# LoRa_1W_Breakout.net
KiCad netlist of a schematic drawn in EAGLE
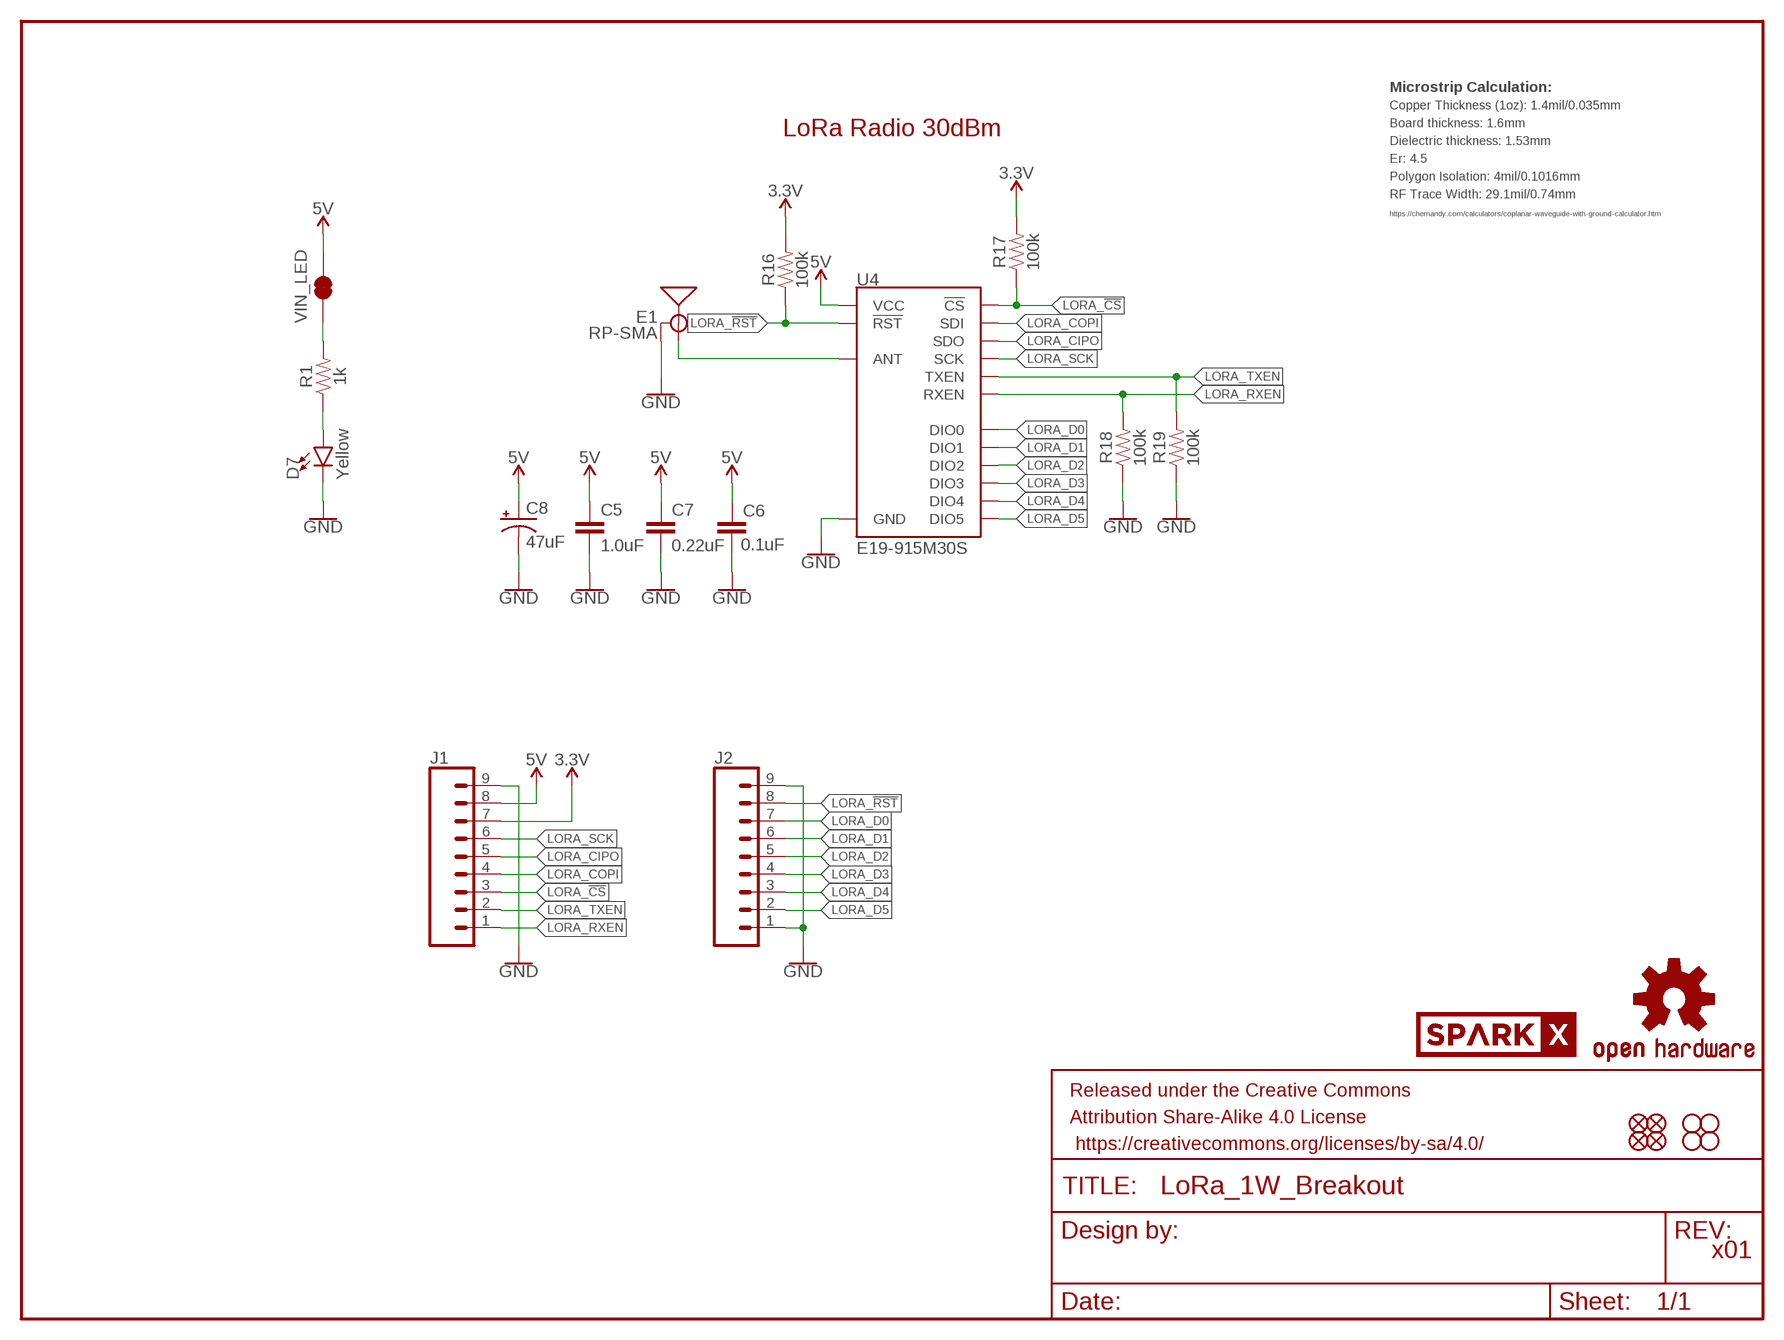
[diagram p0: schematic, sheet 1]

(export (version "E")
  (design (tool "Eeschema 10.0.6"))
  (components
    (comp (ref "C5")
      (value "1.0uF")
      (footprint "eagle-import:0603")
      (libsource (lib "eagle-import") (part "1.0UF-0603-16V-10%"))
    )
    (comp (ref "C6")
      (value "0.1uF")
      (footprint "eagle-import:0603")
      (libsource (lib "eagle-import") (part "0.1UF-0603-25V-(+80/-20%)"))
    )
    (comp (ref "C7")
      (value "0.22uF")
      (footprint "eagle-import:0603")
      (libsource (lib "eagle-import") (part "0.22UF-0603-25V-10%"))
    )
    (comp (ref "C8")
      (value "47uF")
      (footprint "eagle-import:EIA3528")
      (libsource (lib "eagle-import") (part "47UF-POLAR-EIA3528-10V-10%"))
    )
    (comp (ref "D7")
      (value "Yellow")
      (footprint "eagle-import:LED-0603")
      (libsource (lib "eagle-import") (part "LED-YELLOW0603"))
    )
    (comp (ref "E1")
      (value "RP-SMA")
      (footprint "eagle-import:SMA-EDGE")
      (libsource (lib "eagle-import") (part "ANTENNA-SMA-GROUNDEDEDGE_RPSMA"))
    )
    (comp (ref "FD1")
      (value "FIDUCIALUFIDUCIAL")
      (footprint "eagle-import:FIDUCIAL-MICRO")
      (libsource (lib "eagle-import") (part "FIDUCIALUFIDUCIAL"))
    )
    (comp (ref "FD2")
      (value "FIDUCIALUFIDUCIAL")
      (footprint "eagle-import:FIDUCIAL-MICRO")
      (libsource (lib "eagle-import") (part "FIDUCIALUFIDUCIAL"))
    )
    (comp (ref "FD3")
      (value "FIDUCIALUFIDUCIAL")
      (footprint "eagle-import:FIDUCIAL-MICRO")
      (libsource (lib "eagle-import") (part "FIDUCIALUFIDUCIAL"))
    )
    (comp (ref "FD4")
      (value "FIDUCIALUFIDUCIAL")
      (footprint "eagle-import:FIDUCIAL-MICRO")
      (libsource (lib "eagle-import") (part "FIDUCIALUFIDUCIAL"))
    )
    (comp (ref "FRAME2")
      (value "FRAME-LETTER")
      (footprint "eagle-import:CREATIVE_COMMONS")
      (libsource (lib "eagle-import") (part "FRAME-LETTER"))
    )
    (comp (ref "H1")
      (value "STAND-OFF")
      (footprint "eagle-import:STAND-OFF")
      (libsource (lib "eagle-import") (part "STAND-OFF"))
    )
    (comp (ref "H2")
      (value "STAND-OFF")
      (footprint "eagle-import:STAND-OFF")
      (libsource (lib "eagle-import") (part "STAND-OFF"))
    )
    (comp (ref "H3")
      (value "STAND-OFF")
      (footprint "eagle-import:STAND-OFF")
      (libsource (lib "eagle-import") (part "STAND-OFF"))
    )
    (comp (ref "H4")
      (value "STAND-OFF")
      (footprint "eagle-import:STAND-OFF")
      (libsource (lib "eagle-import") (part "STAND-OFF"))
    )
    (comp (ref "J1")
      (value "CONN_09NO_SILK")
      (footprint "eagle-import:1X09_NO_SILK")
      (libsource (lib "eagle-import") (part "CONN_09NO_SILK"))
    )
    (comp (ref "J2")
      (value "CONN_09NO_SILK")
      (footprint "eagle-import:1X09_NO_SILK")
      (libsource (lib "eagle-import") (part "CONN_09NO_SILK"))
    )
    (comp (ref "LOGO3")
      (value "OSHW-LOGOMINI")
      (footprint "eagle-import:OSHW-LOGO-MINI")
      (libsource (lib "eagle-import") (part "OSHW-LOGOMINI"))
    )
    (comp (ref "R1")
      (value "1k")
      (footprint "eagle-import:0603")
      (libsource (lib "eagle-import") (part "1KOHM-0603-1/10W-1%"))
    )
    (comp (ref "R16")
      (value "100k")
      (footprint "eagle-import:0603")
      (libsource (lib "eagle-import") (part "100KOHM-0603-1/10W-1%"))
    )
    (comp (ref "R17")
      (value "100k")
      (footprint "eagle-import:0603")
      (libsource (lib "eagle-import") (part "100KOHM-0603-1/10W-1%"))
    )
    (comp (ref "R18")
      (value "100k")
      (footprint "eagle-import:0603")
      (libsource (lib "eagle-import") (part "100KOHM-0603-1/10W-1%"))
    )
    (comp (ref "R19")
      (value "100k")
      (footprint "eagle-import:0603")
      (libsource (lib "eagle-import") (part "100KOHM-0603-1/10W-1%"))
    )
    (comp (ref "U$5")
      (value "SPARKX-LOGO5")
      (footprint "eagle-import:SPARKX-LARGE")
      (libsource (lib "eagle-import") (part "SPARKX-LOGO5"))
    )
    (comp (ref "U4")
      (value "E19-915M30S")
      (footprint "eagle-import:E19-915MS1W")
      (libsource (lib "eagle-import") (part "E19-915MS1W"))
    )
    (comp (ref "VIN_LED")
      (value "JUMPER-SMT_2_NC_TRACE_SILK")
      (footprint "eagle-import:SMT-JUMPER_2_NC_TRACE_SILK")
      (libsource (lib "eagle-import") (part "JUMPER-SMT_2_NC_TRACE_SILK"))
    )
  )
  (nets
    (net (code "1") (name "/LORA_~{CS}") (class "Default")
      (node (ref "J1") (pin "3") (pinfunction "3_3") (pintype "passive"))
      (node (ref "R17") (pin "1") (pinfunction "1_1") (pintype "passive"))
      (node (ref "U4") (pin "15") (pinfunction "~{CS}_15") (pintype "bidirectional"))
    )
    (net (code "2") (name "/LORA_~{RST}") (class "Default")
      (node (ref "J2") (pin "8") (pinfunction "8_8") (pintype "passive"))
      (node (ref "R16") (pin "1") (pinfunction "1_1") (pintype "passive"))
      (node (ref "U4") (pin "8") (pinfunction "~{RST}_8") (pintype "bidirectional"))
    )
    (net (code "3") (name "3.3V") (class "Default")
      (node (ref "J1") (pin "7") (pinfunction "7_7") (pintype "passive"))
      (node (ref "R16") (pin "2") (pinfunction "2_2") (pintype "passive"))
      (node (ref "R17") (pin "2") (pinfunction "2_2") (pintype "passive"))
    )
    (net (code "4") (name "5V") (class "Default")
      (node (ref "C5") (pin "1") (pinfunction "1_1") (pintype "passive"))
      (node (ref "C6") (pin "1") (pinfunction "1_1") (pintype "passive"))
      (node (ref "C7") (pin "1") (pinfunction "1_1") (pintype "passive"))
      (node (ref "C8") (pin "A") (pinfunction "+_A") (pintype "passive"))
      (node (ref "J1") (pin "8") (pinfunction "8_8") (pintype "passive"))
      (node (ref "U4") (pin "11") (pinfunction "VCC_11") (pintype "bidirectional"))
      (node (ref "VIN_LED") (pin "2") (pinfunction "2_2") (pintype "passive"))
    )
    (net (code "5") (name "GND") (class "Default")
      (node (ref "C5") (pin "2") (pinfunction "2_2") (pintype "passive"))
      (node (ref "C6") (pin "2") (pinfunction "2_2") (pintype "passive"))
      (node (ref "C7") (pin "2") (pinfunction "2_2") (pintype "passive"))
      (node (ref "C8") (pin "C") (pinfunction "-_C") (pintype "passive"))
      (node (ref "D7") (pin "C") (pinfunction "C_C") (pintype "passive"))
      (node (ref "E1") (pin "GND@0") (pinfunction "GND_GND@0") (pintype "bidirectional"))
      (node (ref "E1") (pin "GND@1") (pinfunction "GND_GND@1") (pintype "bidirectional"))
      (node (ref "E1") (pin "GND@2") (pinfunction "GND_GND@2") (pintype "bidirectional"))
      (node (ref "E1") (pin "GND@3") (pinfunction "GND_GND@3") (pintype "bidirectional"))
      (node (ref "J1") (pin "9") (pinfunction "9_9") (pintype "passive"))
      (node (ref "J2") (pin "1") (pinfunction "1_1") (pintype "passive"))
      (node (ref "J2") (pin "9") (pinfunction "9_9") (pintype "passive"))
      (node (ref "R18") (pin "1") (pinfunction "1_1") (pintype "passive"))
      (node (ref "R19") (pin "1") (pinfunction "1_1") (pintype "passive"))
      (node (ref "U4") (pin "1") (pinfunction "GND_1") (pintype "bidirectional"))
      (node (ref "U4") (pin "10") (pinfunction "GND_10") (pintype "bidirectional"))
      (node (ref "U4") (pin "18") (pinfunction "GND_18") (pintype "bidirectional"))
      (node (ref "U4") (pin "20") (pinfunction "GND_20") (pintype "bidirectional"))
      (node (ref "U4") (pin "21") (pinfunction "GND_21") (pintype "bidirectional"))
      (node (ref "U4") (pin "22") (pinfunction "GND_22") (pintype "bidirectional"))
      (node (ref "U4") (pin "9") (pinfunction "GND_9") (pintype "bidirectional"))
    )
    (net (code "6") (name "LORA_CIPO") (class "Default")
      (node (ref "J1") (pin "5") (pinfunction "5_5") (pintype "passive"))
      (node (ref "U4") (pin "13") (pinfunction "SDO_13") (pintype "bidirectional"))
    )
    (net (code "7") (name "LORA_COPI") (class "Default")
      (node (ref "J1") (pin "4") (pinfunction "4_4") (pintype "passive"))
      (node (ref "U4") (pin "14") (pinfunction "SDI_14") (pintype "bidirectional"))
    )
    (net (code "8") (name "LORA_D0") (class "Default")
      (node (ref "J2") (pin "7") (pinfunction "7_7") (pintype "passive"))
      (node (ref "U4") (pin "7") (pinfunction "DIO0_7") (pintype "bidirectional"))
    )
    (net (code "9") (name "LORA_D1") (class "Default")
      (node (ref "J2") (pin "6") (pinfunction "6_6") (pintype "passive"))
      (node (ref "U4") (pin "6") (pinfunction "DIO1_6") (pintype "bidirectional"))
    )
    (net (code "10") (name "LORA_D2") (class "Default")
      (node (ref "J2") (pin "5") (pinfunction "5_5") (pintype "passive"))
      (node (ref "U4") (pin "5") (pinfunction "DIO2_5") (pintype "bidirectional"))
    )
    (net (code "11") (name "LORA_D3") (class "Default")
      (node (ref "J2") (pin "4") (pinfunction "4_4") (pintype "passive"))
      (node (ref "U4") (pin "4") (pinfunction "DIO3_4") (pintype "bidirectional"))
    )
    (net (code "12") (name "LORA_D4") (class "Default")
      (node (ref "J2") (pin "3") (pinfunction "3_3") (pintype "passive"))
      (node (ref "U4") (pin "3") (pinfunction "DIO4_3") (pintype "bidirectional"))
    )
    (net (code "13") (name "LORA_D5") (class "Default")
      (node (ref "J2") (pin "2") (pinfunction "2_2") (pintype "passive"))
      (node (ref "U4") (pin "2") (pinfunction "DIO5_2") (pintype "bidirectional"))
    )
    (net (code "14") (name "LORA_RXEN") (class "Default")
      (node (ref "J1") (pin "1") (pinfunction "1_1") (pintype "passive"))
      (node (ref "R18") (pin "2") (pinfunction "2_2") (pintype "passive"))
      (node (ref "U4") (pin "17") (pinfunction "RXEN_17") (pintype "bidirectional"))
    )
    (net (code "15") (name "LORA_SCK") (class "Default")
      (node (ref "J1") (pin "6") (pinfunction "6_6") (pintype "passive"))
      (node (ref "U4") (pin "12") (pinfunction "SCK_12") (pintype "bidirectional"))
    )
    (net (code "16") (name "LORA_TXEN") (class "Default")
      (node (ref "J1") (pin "2") (pinfunction "2_2") (pintype "passive"))
      (node (ref "R19") (pin "2") (pinfunction "2_2") (pintype "passive"))
      (node (ref "U4") (pin "16") (pinfunction "TXEN_16") (pintype "bidirectional"))
    )
    (net (code "17") (name "Net-(D7-PadA)") (class "Default")
      (node (ref "D7") (pin "A") (pinfunction "A_A") (pintype "passive"))
      (node (ref "R1") (pin "1") (pinfunction "1_1") (pintype "passive"))
    )
    (net (code "18") (name "Net-(E1-SIGNAL)") (class "Default")
      (node (ref "E1") (pin "SIG") (pinfunction "SIGNAL_SIG") (pintype "bidirectional"))
      (node (ref "U4") (pin "19") (pinfunction "ANT_19") (pintype "bidirectional"))
    )
    (net (code "19") (name "Net-(R1-Pad2)") (class "Default")
      (node (ref "R1") (pin "2") (pinfunction "2_2") (pintype "passive"))
      (node (ref "VIN_LED") (pin "1") (pinfunction "1_1") (pintype "passive"))
    )
  )
)
